# Memory.net
KiCad netlist of a schematic drawn in Altium Designer
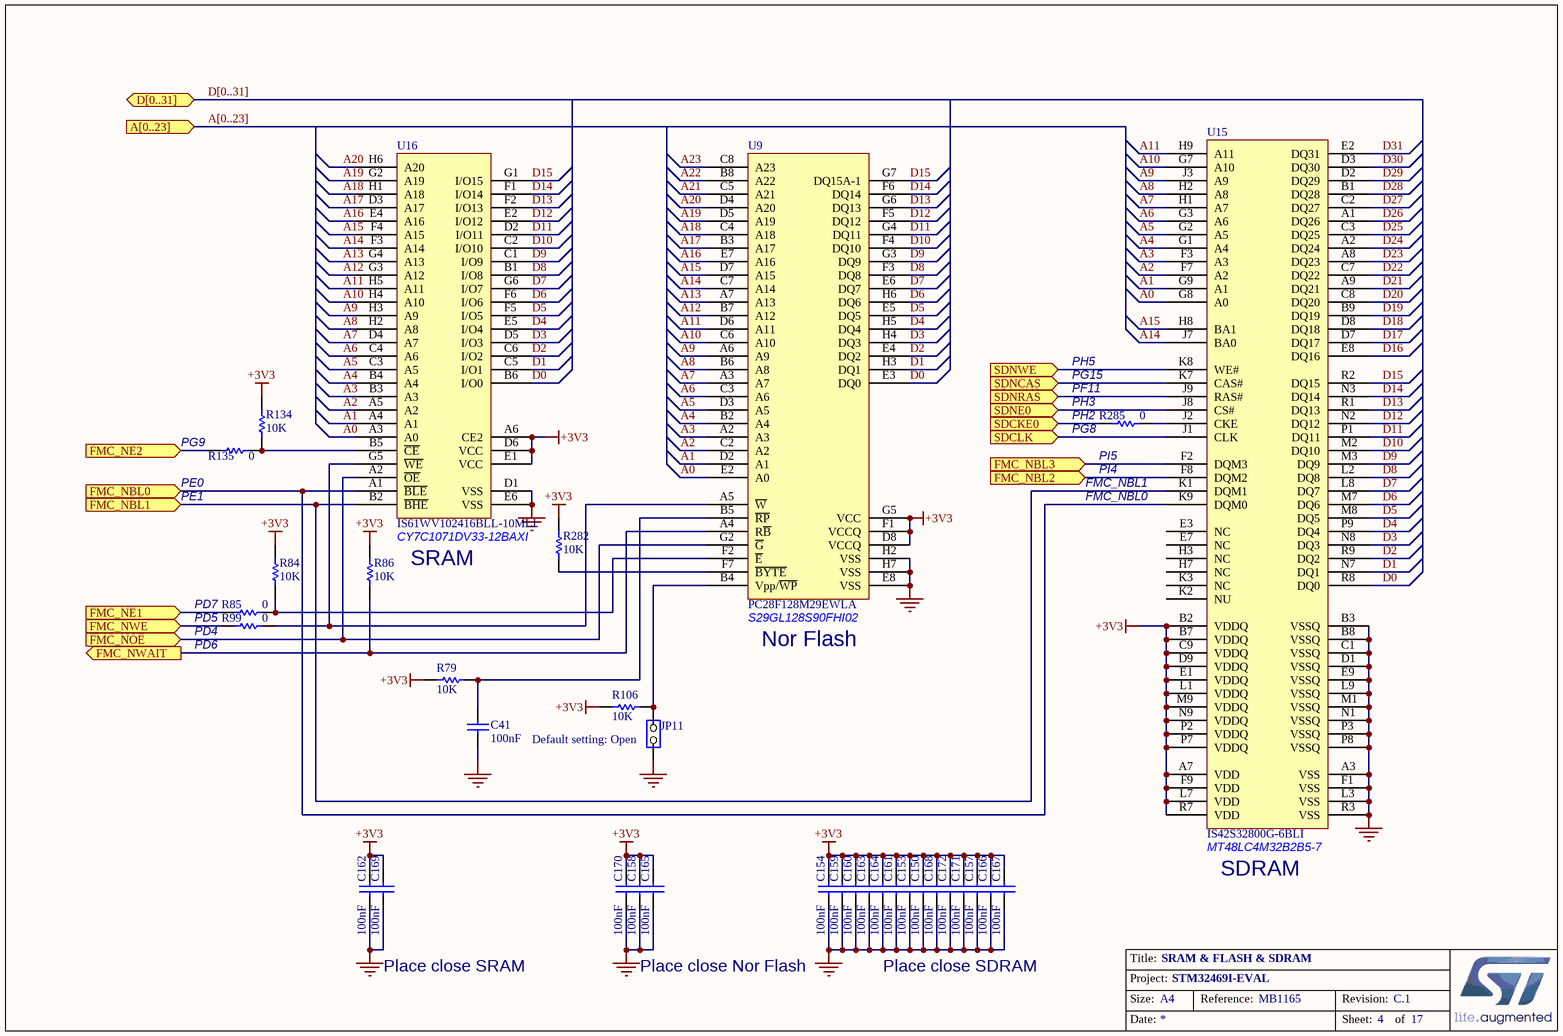
[diagram p0: Memory.SchDoc]

(export (version "E")
  (design (tool "Eeschema 10.0.6"))
  (components
    (comp (ref "C41")
      (value "100nF")
      (footprint "0603C")
      (description "Capacitor")
      (fields (field (name "PUBLISHER") "Altium Limited"))
      (libsource (lib "Miscellaneous Devices") (part "Cap"))
    )
    (comp (ref "C150")
      (value "100nF")
      (footprint "0603C")
      (description "Capacitor")
      (fields (field (name "PUBLISHER") "Altium Limited"))
      (libsource (lib "Miscellaneous Devices") (part "Cap"))
    )
    (comp (ref "C153")
      (value "100nF")
      (footprint "0603C")
      (description "Capacitor")
      (fields (field (name "PUBLISHER") "Altium Limited"))
      (libsource (lib "Miscellaneous Devices") (part "Cap"))
    )
    (comp (ref "C154")
      (value "100nF")
      (footprint "0603C")
      (description "Capacitor")
      (fields (field (name "PUBLISHER") "Altium Limited"))
      (libsource (lib "Miscellaneous Devices") (part "Cap"))
    )
    (comp (ref "C157")
      (value "100nF")
      (footprint "0603C")
      (description "Capacitor")
      (fields (field (name "PUBLISHER") "Altium Limited"))
      (libsource (lib "Miscellaneous Devices") (part "Cap"))
    )
    (comp (ref "C158")
      (value "100nF")
      (footprint "0603C")
      (description "Capacitor")
      (fields (field (name "PUBLISHER") "Altium Limited"))
      (libsource (lib "Miscellaneous Devices") (part "Cap"))
    )
    (comp (ref "C159")
      (value "100nF")
      (footprint "0603C")
      (description "Capacitor")
      (fields (field (name "PUBLISHER") "Altium Limited"))
      (libsource (lib "Miscellaneous Devices") (part "Cap"))
    )
    (comp (ref "C160")
      (value "100nF")
      (footprint "0603C")
      (description "Capacitor")
      (fields (field (name "PUBLISHER") "Altium Limited"))
      (libsource (lib "Miscellaneous Devices") (part "Cap"))
    )
    (comp (ref "C161")
      (value "100nF")
      (footprint "0603C")
      (description "Capacitor")
      (fields (field (name "PUBLISHER") "Altium Limited"))
      (libsource (lib "Miscellaneous Devices") (part "Cap"))
    )
    (comp (ref "C162")
      (value "100nF")
      (footprint "0603C")
      (description "Capacitor")
      (fields (field (name "PUBLISHER") "Altium Limited"))
      (libsource (lib "Miscellaneous Devices") (part "Cap"))
    )
    (comp (ref "C163")
      (value "100nF")
      (footprint "0603C")
      (description "Capacitor")
      (fields (field (name "PUBLISHER") "Altium Limited"))
      (libsource (lib "Miscellaneous Devices") (part "Cap"))
    )
    (comp (ref "C164")
      (value "100nF")
      (footprint "0603C")
      (description "Capacitor")
      (fields (field (name "PUBLISHER") "Altium Limited"))
      (libsource (lib "Miscellaneous Devices") (part "Cap"))
    )
    (comp (ref "C165")
      (value "100nF")
      (footprint "0603C")
      (description "Capacitor")
      (fields (field (name "PUBLISHER") "Altium Limited"))
      (libsource (lib "Miscellaneous Devices") (part "Cap"))
    )
    (comp (ref "C166")
      (value "100nF")
      (footprint "0603C")
      (description "Capacitor")
      (fields (field (name "PUBLISHER") "Altium Limited"))
      (libsource (lib "Miscellaneous Devices") (part "Cap"))
    )
    (comp (ref "C167")
      (value "100nF")
      (footprint "0603C")
      (description "Capacitor")
      (fields (field (name "PUBLISHER") "Altium Limited"))
      (libsource (lib "Miscellaneous Devices") (part "Cap"))
    )
    (comp (ref "C168")
      (value "100nF")
      (footprint "0603C")
      (description "Capacitor")
      (fields (field (name "PUBLISHER") "Altium Limited"))
      (libsource (lib "Miscellaneous Devices") (part "Cap"))
    )
    (comp (ref "C169")
      (value "100nF")
      (footprint "0603C")
      (description "Capacitor")
      (fields (field (name "PUBLISHER") "Altium Limited"))
      (libsource (lib "Miscellaneous Devices") (part "Cap"))
    )
    (comp (ref "C170")
      (value "100nF")
      (footprint "0603C")
      (description "Capacitor")
      (fields (field (name "PUBLISHER") "Altium Limited"))
      (libsource (lib "Miscellaneous Devices") (part "Cap"))
    )
    (comp (ref "C171")
      (value "100nF")
      (footprint "0603C")
      (description "Capacitor")
      (fields (field (name "PUBLISHER") "Altium Limited"))
      (libsource (lib "Miscellaneous Devices") (part "Cap"))
    )
    (comp (ref "C172")
      (value "100nF")
      (footprint "0603C")
      (description "Capacitor")
      (fields (field (name "PUBLISHER") "Altium Limited"))
      (libsource (lib "Miscellaneous Devices") (part "Cap"))
    )
    (comp (ref "JP11") (value "~") (footprint "SIP2") (libsource (lib "*") (part "JP2")))
    (comp (ref "R79")
      (value "10K")
      (footprint "0603R")
      (description "Resistor")
      (fields (field (name "PUBLISHER") "Altium Limited"))
      (libsource (lib "Miscellaneous Devices") (part "Res1"))
    )
    (comp (ref "R84")
      (value "10K")
      (footprint "0603R")
      (description "Resistor")
      (fields (field (name "PUBLISHER") "Altium Limited"))
      (libsource (lib "Miscellaneous Devices") (part "Res1"))
    )
    (comp (ref "R85")
      (value "0")
      (footprint "0603R")
      (description "Resistor")
      (fields (field (name "PUBLISHER") "Altium Limited"))
      (libsource (lib "Miscellaneous Devices") (part "Res1"))
    )
    (comp (ref "R86")
      (value "10K")
      (footprint "0603R")
      (description "Resistor")
      (fields (field (name "PUBLISHER") "Altium Limited"))
      (libsource (lib "Miscellaneous Devices") (part "Res1"))
    )
    (comp (ref "R99")
      (value "0")
      (footprint "0603R")
      (description "Resistor")
      (fields (field (name "PUBLISHER") "Altium Limited"))
      (libsource (lib "Miscellaneous Devices") (part "Res1"))
    )
    (comp (ref "R106")
      (value "10K")
      (footprint "0603R")
      (description "Resistor")
      (fields (field (name "PUBLISHER") "Altium Limited"))
      (libsource (lib "Miscellaneous Devices") (part "Res1"))
    )
    (comp (ref "R134")
      (value "10K")
      (footprint "0603R")
      (description "Resistor")
      (fields (field (name "PUBLISHER") "Altium Limited"))
      (libsource (lib "Miscellaneous Devices") (part "Res1"))
    )
    (comp (ref "R135")
      (value "0")
      (footprint "0603R")
      (description "Resistor")
      (fields (field (name "PUBLISHER") "Altium Limited"))
      (libsource (lib "Miscellaneous Devices") (part "Res1"))
    )
    (comp (ref "R282")
      (value "10K")
      (footprint "0603R")
      (description "Resistor")
      (fields (field (name "PUBLISHER") "Altium Limited"))
      (libsource (lib "Miscellaneous Devices") (part "Res1"))
    )
    (comp (ref "R285")
      (value "0")
      (footprint "0603R")
      (description "Resistor")
      (fields (field (name "PUBLISHER") "Altium Limited"))
      (libsource (lib "Miscellaneous Devices") (part "Res1"))
    )
    (comp (ref "U9")
      (value "PC28F128M29EWLA")
      (footprint "FBGA64_1_11X13")
      (libsource (lib "MB964") (part "M29W128FL70ZA6E"))
    )
    (comp (ref "U15")
      (value "IS42S32800G-6BLI")
      (footprint "FBGA90_0R8_8X13")
      (libsource (lib "mb1045") (part "MT48LC4M32B2B5"))
    )
    (comp (ref "U16")
      (value "IS61WV102416BLL-10MLI")
      (footprint "BGA48_0R75_9X11")
      (libsource (lib "MB901") (part "IS61WV102416BLL-10MLI"))
    )
  )
  (nets
    (net (code "1") (name "+3V3") (class "Default")
      (node (ref "C150") (pin "1") (pinfunction "1_1") (pintype "passive"))
      (node (ref "C153") (pin "1") (pinfunction "1_1") (pintype "passive"))
      (node (ref "C154") (pin "1") (pinfunction "1_1") (pintype "passive"))
      (node (ref "C157") (pin "1") (pinfunction "1_1") (pintype "passive"))
      (node (ref "C158") (pin "1") (pinfunction "1_1") (pintype "passive"))
      (node (ref "C159") (pin "1") (pinfunction "1_1") (pintype "passive"))
      (node (ref "C160") (pin "1") (pinfunction "1_1") (pintype "passive"))
      (node (ref "C161") (pin "1") (pinfunction "1_1") (pintype "passive"))
      (node (ref "C162") (pin "1") (pinfunction "1_1") (pintype "passive"))
      (node (ref "C163") (pin "1") (pinfunction "1_1") (pintype "passive"))
      (node (ref "C164") (pin "1") (pinfunction "1_1") (pintype "passive"))
      (node (ref "C165") (pin "1") (pinfunction "1_1") (pintype "passive"))
      (node (ref "C166") (pin "1") (pinfunction "1_1") (pintype "passive"))
      (node (ref "C167") (pin "1") (pinfunction "1_1") (pintype "passive"))
      (node (ref "C168") (pin "1") (pinfunction "1_1") (pintype "passive"))
      (node (ref "C169") (pin "1") (pinfunction "1_1") (pintype "passive"))
      (node (ref "C170") (pin "1") (pinfunction "1_1") (pintype "passive"))
      (node (ref "C171") (pin "1") (pinfunction "1_1") (pintype "passive"))
      (node (ref "C172") (pin "1") (pinfunction "1_1") (pintype "passive"))
      (node (ref "R106") (pin "2") (pinfunction "2_2") (pintype "passive"))
      (node (ref "R134") (pin "2") (pinfunction "2_2") (pintype "passive"))
      (node (ref "R282") (pin "2") (pinfunction "2_2") (pintype "passive"))
      (node (ref "R79") (pin "1") (pinfunction "1_1") (pintype "passive"))
      (node (ref "R84") (pin "2") (pinfunction "2_2") (pintype "passive"))
      (node (ref "R86") (pin "2") (pinfunction "2_2") (pintype "passive"))
      (node (ref "U15") (pin "A7") (pinfunction "VDD_A7") (pintype "passive"))
      (node (ref "U15") (pin "B2") (pinfunction "VDDQ_B2") (pintype "passive"))
      (node (ref "U15") (pin "B7") (pinfunction "VDDQ_B7") (pintype "passive"))
      (node (ref "U15") (pin "C9") (pinfunction "VDDQ_C9") (pintype "passive"))
      (node (ref "U15") (pin "D9") (pinfunction "VDDQ_D9") (pintype "passive"))
      (node (ref "U15") (pin "E1") (pinfunction "VDDQ_E1") (pintype "passive"))
      (node (ref "U15") (pin "F9") (pinfunction "VDD_F9") (pintype "passive"))
      (node (ref "U15") (pin "L1") (pinfunction "VDDQ_L1") (pintype "passive"))
      (node (ref "U15") (pin "L7") (pinfunction "VDD_L7") (pintype "passive"))
      (node (ref "U15") (pin "M9") (pinfunction "VDDQ_M9") (pintype "passive"))
      (node (ref "U15") (pin "N9") (pinfunction "VDDQ_N9") (pintype "passive"))
      (node (ref "U15") (pin "P2") (pinfunction "VDDQ_P2") (pintype "passive"))
      (node (ref "U15") (pin "P7") (pinfunction "VDDQ_P7") (pintype "passive"))
      (node (ref "U15") (pin "R7") (pinfunction "VDD_R7") (pintype "passive"))
      (node (ref "U16") (pin "A6") (pinfunction "CE2_A6") (pintype "passive"))
      (node (ref "U16") (pin "D6") (pinfunction "VCC_D6") (pintype "passive"))
      (node (ref "U16") (pin "E1") (pinfunction "VCC_E1") (pintype "passive"))
      (node (ref "U9") (pin "D8") (pinfunction "VCCQ_D8") (pintype "passive"))
      (node (ref "U9") (pin "F1") (pinfunction "VCCQ_F1") (pintype "passive"))
      (node (ref "U9") (pin "G5") (pinfunction "VCC_G5") (pintype "passive"))
    )
    (net (code "2") (name "/A0") (class "Default")
      (node (ref "U15") (pin "G8") (pinfunction "A0_G8") (pintype "passive"))
      (node (ref "U16") (pin "A3") (pinfunction "A0_A3") (pintype "passive"))
      (node (ref "U9") (pin "E2") (pinfunction "A0_E2") (pintype "passive"))
    )
    (net (code "3") (name "/A1") (class "Default")
      (node (ref "U15") (pin "G9") (pinfunction "A1_G9") (pintype "passive"))
      (node (ref "U16") (pin "A4") (pinfunction "A1_A4") (pintype "passive"))
      (node (ref "U9") (pin "D2") (pinfunction "A1_D2") (pintype "passive"))
    )
    (net (code "4") (name "/A2") (class "Default")
      (node (ref "U15") (pin "F7") (pinfunction "A2_F7") (pintype "passive"))
      (node (ref "U16") (pin "A5") (pinfunction "A2_A5") (pintype "passive"))
      (node (ref "U9") (pin "C2") (pinfunction "A2_C2") (pintype "passive"))
    )
    (net (code "5") (name "/A3") (class "Default")
      (node (ref "U15") (pin "F3") (pinfunction "A3_F3") (pintype "passive"))
      (node (ref "U16") (pin "B3") (pinfunction "A3_B3") (pintype "passive"))
      (node (ref "U9") (pin "A2") (pinfunction "A3_A2") (pintype "passive"))
    )
    (net (code "6") (name "/A4") (class "Default")
      (node (ref "U15") (pin "G1") (pinfunction "A4_G1") (pintype "passive"))
      (node (ref "U16") (pin "B4") (pinfunction "A4_B4") (pintype "passive"))
      (node (ref "U9") (pin "B2") (pinfunction "A4_B2") (pintype "passive"))
    )
    (net (code "7") (name "/A5") (class "Default")
      (node (ref "U15") (pin "G2") (pinfunction "A5_G2") (pintype "passive"))
      (node (ref "U16") (pin "C3") (pinfunction "A5_C3") (pintype "passive"))
      (node (ref "U9") (pin "D3") (pinfunction "A5_D3") (pintype "passive"))
    )
    (net (code "8") (name "/A6") (class "Default")
      (node (ref "U15") (pin "G3") (pinfunction "A6_G3") (pintype "passive"))
      (node (ref "U16") (pin "C4") (pinfunction "A6_C4") (pintype "passive"))
      (node (ref "U9") (pin "C3") (pinfunction "A6_C3") (pintype "passive"))
    )
    (net (code "9") (name "/A7") (class "Default")
      (node (ref "U15") (pin "H1") (pinfunction "A7_H1") (pintype "passive"))
      (node (ref "U16") (pin "D4") (pinfunction "A7_D4") (pintype "passive"))
      (node (ref "U9") (pin "A3") (pinfunction "A7_A3") (pintype "passive"))
    )
    (net (code "10") (name "/A8") (class "Default")
      (node (ref "U15") (pin "H2") (pinfunction "A8_H2") (pintype "passive"))
      (node (ref "U16") (pin "H2") (pinfunction "A8_H2") (pintype "passive"))
      (node (ref "U9") (pin "B6") (pinfunction "A8_B6") (pintype "passive"))
    )
    (net (code "11") (name "/A9") (class "Default")
      (node (ref "U15") (pin "J3") (pinfunction "A9_J3") (pintype "passive"))
      (node (ref "U16") (pin "H3") (pinfunction "A9_H3") (pintype "passive"))
      (node (ref "U9") (pin "A6") (pinfunction "A9_A6") (pintype "passive"))
    )
    (net (code "12") (name "/A10") (class "Default")
      (node (ref "U15") (pin "G7") (pinfunction "A10_G7") (pintype "passive"))
      (node (ref "U16") (pin "H4") (pinfunction "A10_H4") (pintype "passive"))
      (node (ref "U9") (pin "C6") (pinfunction "A10_C6") (pintype "passive"))
    )
    (net (code "13") (name "/A11") (class "Default")
      (node (ref "U15") (pin "H9") (pinfunction "A11_H9") (pintype "passive"))
      (node (ref "U16") (pin "H5") (pinfunction "A11_H5") (pintype "passive"))
      (node (ref "U9") (pin "D6") (pinfunction "A11_D6") (pintype "passive"))
    )
    (net (code "14") (name "/A12") (class "Default")
      (node (ref "U16") (pin "G3") (pinfunction "A12_G3") (pintype "passive"))
      (node (ref "U9") (pin "B7") (pinfunction "A12_B7") (pintype "passive"))
    )
    (net (code "15") (name "/A13") (class "Default")
      (node (ref "U16") (pin "G4") (pinfunction "A13_G4") (pintype "passive"))
      (node (ref "U9") (pin "A7") (pinfunction "A13_A7") (pintype "passive"))
    )
    (net (code "16") (name "/A14") (class "Default")
      (node (ref "U15") (pin "J7") (pinfunction "BA0_J7") (pintype "passive"))
      (node (ref "U16") (pin "F3") (pinfunction "A14_F3") (pintype "passive"))
      (node (ref "U9") (pin "C7") (pinfunction "A14_C7") (pintype "passive"))
    )
    (net (code "17") (name "/A15") (class "Default")
      (node (ref "U15") (pin "H8") (pinfunction "BA1_H8") (pintype "passive"))
      (node (ref "U16") (pin "F4") (pinfunction "A15_F4") (pintype "passive"))
      (node (ref "U9") (pin "D7") (pinfunction "A15_D7") (pintype "passive"))
    )
    (net (code "18") (name "/A16") (class "Default")
      (node (ref "U16") (pin "E4") (pinfunction "A16_E4") (pintype "passive"))
      (node (ref "U9") (pin "E7") (pinfunction "A16_E7") (pintype "passive"))
    )
    (net (code "19") (name "/A17") (class "Default")
      (node (ref "U16") (pin "D3") (pinfunction "A17_D3") (pintype "passive"))
      (node (ref "U9") (pin "B3") (pinfunction "A17_B3") (pintype "passive"))
    )
    (net (code "20") (name "/A18") (class "Default")
      (node (ref "U16") (pin "H1") (pinfunction "A18_H1") (pintype "passive"))
      (node (ref "U9") (pin "C4") (pinfunction "A18_C4") (pintype "passive"))
    )
    (net (code "21") (name "/A19") (class "Default")
      (node (ref "U16") (pin "G2") (pinfunction "A19_G2") (pintype "passive"))
      (node (ref "U9") (pin "D5") (pinfunction "A19_D5") (pintype "passive"))
    )
    (net (code "22") (name "/A20") (class "Default")
      (node (ref "U16") (pin "H6") (pinfunction "A20_H6") (pintype "passive"))
      (node (ref "U9") (pin "D4") (pinfunction "A20_D4") (pintype "passive"))
    )
    (net (code "23") (name "/A21") (class "Default")
      (node (ref "U9") (pin "C5") (pinfunction "A21_C5") (pintype "passive"))
    )
    (net (code "24") (name "/A22") (class "Default")
      (node (ref "U9") (pin "B8") (pinfunction "A22_B8") (pintype "passive"))
    )
    (net (code "25") (name "/A23") (class "Default")
      (node (ref "U9") (pin "C8") (pinfunction "A23_C8") (pintype "passive"))
    )
    (net (code "27") (name "/D0") (class "Default")
      (node (ref "U15") (pin "R8") (pinfunction "DQ0_R8") (pintype "passive"))
      (node (ref "U16") (pin "B6") (pinfunction "I/O0_B6") (pintype "passive"))
      (node (ref "U9") (pin "E3") (pinfunction "DQ0_E3") (pintype "passive"))
    )
    (net (code "28") (name "/D1") (class "Default")
      (node (ref "U15") (pin "N7") (pinfunction "DQ1_N7") (pintype "passive"))
      (node (ref "U16") (pin "C5") (pinfunction "I/O1_C5") (pintype "passive"))
      (node (ref "U9") (pin "H3") (pinfunction "DQ1_H3") (pintype "passive"))
    )
    (net (code "29") (name "/D2") (class "Default")
      (node (ref "U15") (pin "R9") (pinfunction "DQ2_R9") (pintype "passive"))
      (node (ref "U16") (pin "C6") (pinfunction "I/O2_C6") (pintype "passive"))
      (node (ref "U9") (pin "E4") (pinfunction "DQ2_E4") (pintype "passive"))
    )
    (net (code "30") (name "/D3") (class "Default")
      (node (ref "U15") (pin "N8") (pinfunction "DQ3_N8") (pintype "passive"))
      (node (ref "U16") (pin "D5") (pinfunction "I/O3_D5") (pintype "passive"))
      (node (ref "U9") (pin "H4") (pinfunction "DQ3_H4") (pintype "passive"))
    )
    (net (code "31") (name "/D4") (class "Default")
      (node (ref "U15") (pin "P9") (pinfunction "DQ4_P9") (pintype "passive"))
      (node (ref "U16") (pin "E5") (pinfunction "I/O4_E5") (pintype "passive"))
      (node (ref "U9") (pin "H5") (pinfunction "DQ4_H5") (pintype "passive"))
    )
    (net (code "32") (name "/D5") (class "Default")
      (node (ref "U15") (pin "M8") (pinfunction "DQ5_M8") (pintype "passive"))
      (node (ref "U16") (pin "F5") (pinfunction "I/O5_F5") (pintype "passive"))
      (node (ref "U9") (pin "E5") (pinfunction "DQ5_E5") (pintype "passive"))
    )
    (net (code "33") (name "/D6") (class "Default")
      (node (ref "U15") (pin "M7") (pinfunction "DQ6_M7") (pintype "passive"))
      (node (ref "U16") (pin "F6") (pinfunction "I/O6_F6") (pintype "passive"))
      (node (ref "U9") (pin "H6") (pinfunction "DQ6_H6") (pintype "passive"))
    )
    (net (code "34") (name "/D7") (class "Default")
      (node (ref "U15") (pin "L8") (pinfunction "DQ7_L8") (pintype "passive"))
      (node (ref "U16") (pin "G6") (pinfunction "I/O7_G6") (pintype "passive"))
      (node (ref "U9") (pin "E6") (pinfunction "DQ7_E6") (pintype "passive"))
    )
    (net (code "35") (name "/D8") (class "Default")
      (node (ref "U15") (pin "L2") (pinfunction "DQ8_L2") (pintype "passive"))
      (node (ref "U16") (pin "B1") (pinfunction "I/O8_B1") (pintype "passive"))
      (node (ref "U9") (pin "F3") (pinfunction "DQ8_F3") (pintype "passive"))
    )
    (net (code "36") (name "/D9") (class "Default")
      (node (ref "U15") (pin "M3") (pinfunction "DQ9_M3") (pintype "passive"))
      (node (ref "U16") (pin "C1") (pinfunction "I/O9_C1") (pintype "passive"))
      (node (ref "U9") (pin "G3") (pinfunction "DQ9_G3") (pintype "passive"))
    )
    (net (code "37") (name "/D10") (class "Default")
      (node (ref "U15") (pin "M2") (pinfunction "DQ10_M2") (pintype "passive"))
      (node (ref "U16") (pin "C2") (pinfunction "I/O10_C2") (pintype "passive"))
      (node (ref "U9") (pin "F4") (pinfunction "DQ10_F4") (pintype "passive"))
    )
    (net (code "38") (name "/D11") (class "Default")
      (node (ref "U15") (pin "P1") (pinfunction "DQ11_P1") (pintype "passive"))
      (node (ref "U16") (pin "D2") (pinfunction "I/O11_D2") (pintype "passive"))
      (node (ref "U9") (pin "G4") (pinfunction "DQ11_G4") (pintype "passive"))
    )
    (net (code "39") (name "/D12") (class "Default")
      (node (ref "U15") (pin "N2") (pinfunction "DQ12_N2") (pintype "passive"))
      (node (ref "U16") (pin "E2") (pinfunction "I/O12_E2") (pintype "passive"))
      (node (ref "U9") (pin "F5") (pinfunction "DQ12_F5") (pintype "passive"))
    )
    (net (code "40") (name "/D13") (class "Default")
      (node (ref "U15") (pin "R1") (pinfunction "DQ13_R1") (pintype "passive"))
      (node (ref "U16") (pin "F2") (pinfunction "I/O13_F2") (pintype "passive"))
      (node (ref "U9") (pin "G6") (pinfunction "DQ13_G6") (pintype "passive"))
    )
    (net (code "41") (name "/D14") (class "Default")
      (node (ref "U15") (pin "N3") (pinfunction "DQ14_N3") (pintype "passive"))
      (node (ref "U16") (pin "F1") (pinfunction "I/O14_F1") (pintype "passive"))
      (node (ref "U9") (pin "F6") (pinfunction "DQ14_F6") (pintype "passive"))
    )
    (net (code "42") (name "/D15") (class "Default")
      (node (ref "U15") (pin "R2") (pinfunction "DQ15_R2") (pintype "passive"))
      (node (ref "U16") (pin "G1") (pinfunction "I/O15_G1") (pintype "passive"))
      (node (ref "U9") (pin "G7") (pinfunction "DQ15A-1_G7") (pintype "passive"))
    )
    (net (code "43") (name "/D16") (class "Default")
      (node (ref "U15") (pin "E8") (pinfunction "DQ16_E8") (pintype "passive"))
    )
    (net (code "44") (name "/D17") (class "Default")
      (node (ref "U15") (pin "D7") (pinfunction "DQ17_D7") (pintype "passive"))
    )
    (net (code "45") (name "/D18") (class "Default")
      (node (ref "U15") (pin "D8") (pinfunction "DQ18_D8") (pintype "passive"))
    )
    (net (code "46") (name "/D19") (class "Default")
      (node (ref "U15") (pin "B9") (pinfunction "DQ19_B9") (pintype "passive"))
    )
    (net (code "47") (name "/D20") (class "Default")
      (node (ref "U15") (pin "C8") (pinfunction "DQ20_C8") (pintype "passive"))
    )
    (net (code "48") (name "/D21") (class "Default")
      (node (ref "U15") (pin "A9") (pinfunction "DQ21_A9") (pintype "passive"))
    )
    (net (code "49") (name "/D22") (class "Default")
      (node (ref "U15") (pin "C7") (pinfunction "DQ22_C7") (pintype "passive"))
    )
    (net (code "50") (name "/D23") (class "Default")
      (node (ref "U15") (pin "A8") (pinfunction "DQ23_A8") (pintype "passive"))
    )
    (net (code "51") (name "/D24") (class "Default")
      (node (ref "U15") (pin "A2") (pinfunction "DQ24_A2") (pintype "passive"))
    )
    (net (code "52") (name "/D25") (class "Default")
      (node (ref "U15") (pin "C3") (pinfunction "DQ25_C3") (pintype "passive"))
    )
    (net (code "53") (name "/D26") (class "Default")
      (node (ref "U15") (pin "A1") (pinfunction "DQ26_A1") (pintype "passive"))
    )
    (net (code "54") (name "/D27") (class "Default")
      (node (ref "U15") (pin "C2") (pinfunction "DQ27_C2") (pintype "passive"))
    )
    (net (code "55") (name "/D28") (class "Default")
      (node (ref "U15") (pin "B1") (pinfunction "DQ28_B1") (pintype "passive"))
    )
    (net (code "56") (name "/D29") (class "Default")
      (node (ref "U15") (pin "D2") (pinfunction "DQ29_D2") (pintype "passive"))
    )
    (net (code "57") (name "/D30") (class "Default")
      (node (ref "U15") (pin "D3") (pinfunction "DQ30_D3") (pintype "passive"))
    )
    (net (code "58") (name "/D31") (class "Default")
      (node (ref "U15") (pin "E2") (pinfunction "DQ31_E2") (pintype "passive"))
    )
    (net (code "60") (name "/FMC_NBL0") (class "Default")
      (node (ref "U15") (pin "K9") (pinfunction "DQM0_K9") (pintype "passive"))
      (node (ref "U16") (pin "A1") (pinfunction "~{BLE}_A1") (pintype "passive"))
    )
    (net (code "61") (name "/FMC_NBL1") (class "Default")
      (node (ref "U15") (pin "K1") (pinfunction "DQM1_K1") (pintype "passive"))
      (node (ref "U16") (pin "B2") (pinfunction "~{BHE}_B2") (pintype "passive"))
    )
    (net (code "62") (name "/FMC_NBL2") (class "Default")
      (node (ref "U15") (pin "F8") (pinfunction "DQM2_F8") (pintype "passive"))
    )
    (net (code "63") (name "/FMC_NBL3") (class "Default")
      (node (ref "U15") (pin "F2") (pinfunction "DQM3_F2") (pintype "passive"))
    )
    (net (code "64") (name "/FMC_NE1") (class "Default")
      (node (ref "R85") (pin "2") (pinfunction "2_2") (pintype "passive"))
    )
    (net (code "65") (name "/FMC_NE2") (class "Default")
      (node (ref "R135") (pin "2") (pinfunction "2_2") (pintype "passive"))
    )
    (net (code "66") (name "/FMC_NOE") (class "Default")
      (node (ref "U16") (pin "A2") (pinfunction "~{OE}_A2") (pintype "passive"))
      (node (ref "U9") (pin "G2") (pinfunction "~{G}_G2") (pintype "passive"))
    )
    (net (code "67") (name "/FMC_NWAIT") (class "Default")
      (node (ref "R86") (pin "1") (pinfunction "1_1") (pintype "passive"))
      (node (ref "U9") (pin "A4") (pinfunction "R~{B}_A4") (pintype "passive"))
    )
    (net (code "68") (name "/FMC_NWE") (class "Default")
      (node (ref "R99") (pin "2") (pinfunction "2_2") (pintype "passive"))
    )
    (net (code "69") (name "/SDCKE0") (class "Default")
      (node (ref "R285") (pin "2") (pinfunction "2_2") (pintype "passive"))
    )
    (net (code "70") (name "/SDCLK") (class "Default")
      (node (ref "U15") (pin "J1") (pinfunction "CLK_J1") (pintype "passive"))
    )
    (net (code "71") (name "/SDNCAS") (class "Default")
      (node (ref "U15") (pin "K7") (pinfunction "CAS#_K7") (pintype "passive"))
    )
    (net (code "72") (name "/SDNE0") (class "Default")
      (node (ref "U15") (pin "J8") (pinfunction "CS#_J8") (pintype "passive"))
    )
    (net (code "73") (name "/SDNRAS") (class "Default")
      (node (ref "U15") (pin "J9") (pinfunction "RAS#_J9") (pintype "passive"))
    )
    (net (code "74") (name "/SDNWE") (class "Default")
      (node (ref "U15") (pin "K8") (pinfunction "WE#_K8") (pintype "passive"))
    )
    (net (code "75") (name "GND") (class "Default")
      (node (ref "C150") (pin "2") (pinfunction "2_2") (pintype "passive"))
      (node (ref "C153") (pin "2") (pinfunction "2_2") (pintype "passive"))
      (node (ref "C154") (pin "2") (pinfunction "2_2") (pintype "passive"))
      (node (ref "C157") (pin "2") (pinfunction "2_2") (pintype "passive"))
      (node (ref "C158") (pin "2") (pinfunction "2_2") (pintype "passive"))
      (node (ref "C159") (pin "2") (pinfunction "2_2") (pintype "passive"))
      (node (ref "C160") (pin "2") (pinfunction "2_2") (pintype "passive"))
      (node (ref "C161") (pin "2") (pinfunction "2_2") (pintype "passive"))
      (node (ref "C162") (pin "2") (pinfunction "2_2") (pintype "passive"))
      (node (ref "C163") (pin "2") (pinfunction "2_2") (pintype "passive"))
      (node (ref "C164") (pin "2") (pinfunction "2_2") (pintype "passive"))
      (node (ref "C165") (pin "2") (pinfunction "2_2") (pintype "passive"))
      (node (ref "C166") (pin "2") (pinfunction "2_2") (pintype "passive"))
      (node (ref "C167") (pin "2") (pinfunction "2_2") (pintype "passive"))
      (node (ref "C168") (pin "2") (pinfunction "2_2") (pintype "passive"))
      (node (ref "C169") (pin "2") (pinfunction "2_2") (pintype "passive"))
      (node (ref "C170") (pin "2") (pinfunction "2_2") (pintype "passive"))
      (node (ref "C171") (pin "2") (pinfunction "2_2") (pintype "passive"))
      (node (ref "C172") (pin "2") (pinfunction "2_2") (pintype "passive"))
      (node (ref "C41") (pin "2") (pinfunction "2_2") (pintype "passive"))
      (node (ref "JP11") (pin "1") (pinfunction "COMMON_1") (pintype "passive"))
      (node (ref "U15") (pin "A3") (pinfunction "VSS_A3") (pintype "passive"))
      (node (ref "U15") (pin "B3") (pinfunction "VSSQ_B3") (pintype "passive"))
      (node (ref "U15") (pin "B8") (pinfunction "VSSQ_B8") (pintype "passive"))
      (node (ref "U15") (pin "C1") (pinfunction "VSSQ_C1") (pintype "passive"))
      (node (ref "U15") (pin "D1") (pinfunction "VSSQ_D1") (pintype "passive"))
      (node (ref "U15") (pin "E9") (pinfunction "VSSQ_E9") (pintype "passive"))
      (node (ref "U15") (pin "F1") (pinfunction "VSS_F1") (pintype "passive"))
      (node (ref "U15") (pin "L3") (pinfunction "VSS_L3") (pintype "passive"))
      (node (ref "U15") (pin "L9") (pinfunction "VSSQ_L9") (pintype "passive"))
      (node (ref "U15") (pin "M1") (pinfunction "VSSQ_M1") (pintype "passive"))
      (node (ref "U15") (pin "N1") (pinfunction "VSSQ_N1") (pintype "passive"))
      (node (ref "U15") (pin "P3") (pinfunction "VSSQ_P3") (pintype "passive"))
      (node (ref "U15") (pin "P8") (pinfunction "VSSQ_P8") (pintype "passive"))
      (node (ref "U15") (pin "R3") (pinfunction "VSS_R3") (pintype "passive"))
      (node (ref "U16") (pin "D1") (pinfunction "VSS_D1") (pintype "passive"))
      (node (ref "U16") (pin "E6") (pinfunction "VSS_E6") (pintype "passive"))
      (node (ref "U9") (pin "E8") (pinfunction "VSS_E8") (pintype "passive"))
      (node (ref "U9") (pin "H2") (pinfunction "VSS_H2") (pintype "passive"))
      (node (ref "U9") (pin "H7") (pinfunction "VSS_H7") (pintype "passive"))
    )
    (net (code "76") (name "Net-(JP11-NO)") (class "Default")
      (node (ref "JP11") (pin "2") (pinfunction "NO_2") (pintype "passive"))
      (node (ref "R106") (pin "1") (pinfunction "1_1") (pintype "passive"))
      (node (ref "U9") (pin "B4") (pinfunction "Vpp/~{WP}_B4") (pintype "passive"))
    )
    (net (code "77") (name "Net-(U9-~{BYTE})") (class "Default")
      (node (ref "R282") (pin "1") (pinfunction "1_1") (pintype "passive"))
      (node (ref "U9") (pin "F7") (pinfunction "~{BYTE}_F7") (pintype "passive"))
    )
    (net (code "78") (name "Net-(U9-~{E})") (class "Default")
      (node (ref "R84") (pin "1") (pinfunction "1_1") (pintype "passive"))
      (node (ref "R85") (pin "1") (pinfunction "1_1") (pintype "passive"))
      (node (ref "U9") (pin "F2") (pinfunction "~{E}_F2") (pintype "passive"))
    )
    (net (code "79") (name "Net-(U9-~{RP})") (class "Default")
      (node (ref "C41") (pin "1") (pinfunction "1_1") (pintype "passive"))
      (node (ref "R79") (pin "2") (pinfunction "2_2") (pintype "passive"))
      (node (ref "U9") (pin "B5") (pinfunction "~{RP}_B5") (pintype "passive"))
    )
    (net (code "80") (name "Net-(U15-CKE)") (class "Default")
      (node (ref "R285") (pin "1") (pinfunction "1_1") (pintype "passive"))
      (node (ref "U15") (pin "J2") (pinfunction "CKE_J2") (pintype "passive"))
    )
    (net (code "81") (name "Net-(U16-~{CE})") (class "Default")
      (node (ref "R134") (pin "1") (pinfunction "1_1") (pintype "passive"))
      (node (ref "R135") (pin "1") (pinfunction "1_1") (pintype "passive"))
      (node (ref "U16") (pin "B5") (pinfunction "~{CE}_B5") (pintype "passive"))
    )
    (net (code "82") (name "Net-(U16-~{WE})") (class "Default")
      (node (ref "R99") (pin "1") (pinfunction "1_1") (pintype "passive"))
      (node (ref "U16") (pin "G5") (pinfunction "~{WE}_G5") (pintype "passive"))
      (node (ref "U9") (pin "A5") (pinfunction "~{W}_A5") (pintype "passive"))
    )
    (net (code "83") (name "unconnected-(U15-NC-PadE3)") (class "Default")
      (node (ref "U15") (pin "E3") (pinfunction "NC_E3") (pintype "passive"))
    )
    (net (code "84") (name "unconnected-(U15-NC-PadE7)") (class "Default")
      (node (ref "U15") (pin "E7") (pinfunction "NC_E7") (pintype "passive"))
    )
    (net (code "85") (name "unconnected-(U15-NC-PadH3)") (class "Default")
      (node (ref "U15") (pin "H3") (pinfunction "NC_H3") (pintype "passive"))
    )
    (net (code "86") (name "unconnected-(U15-NC-PadH7)") (class "Default")
      (node (ref "U15") (pin "H7") (pinfunction "NC_H7") (pintype "passive"))
    )
    (net (code "87") (name "unconnected-(U15-NC-PadK3)") (class "Default")
      (node (ref "U15") (pin "K3") (pinfunction "NC_K3") (pintype "passive"))
    )
    (net (code "88") (name "unconnected-(U15-NU-PadK2)") (class "Default")
      (node (ref "U15") (pin "K2") (pinfunction "NU_K2") (pintype "passive"))
    )
  )
)
